# METR4810_Schematic.net
KiCad netlist of a schematic drawn in Altium Designer
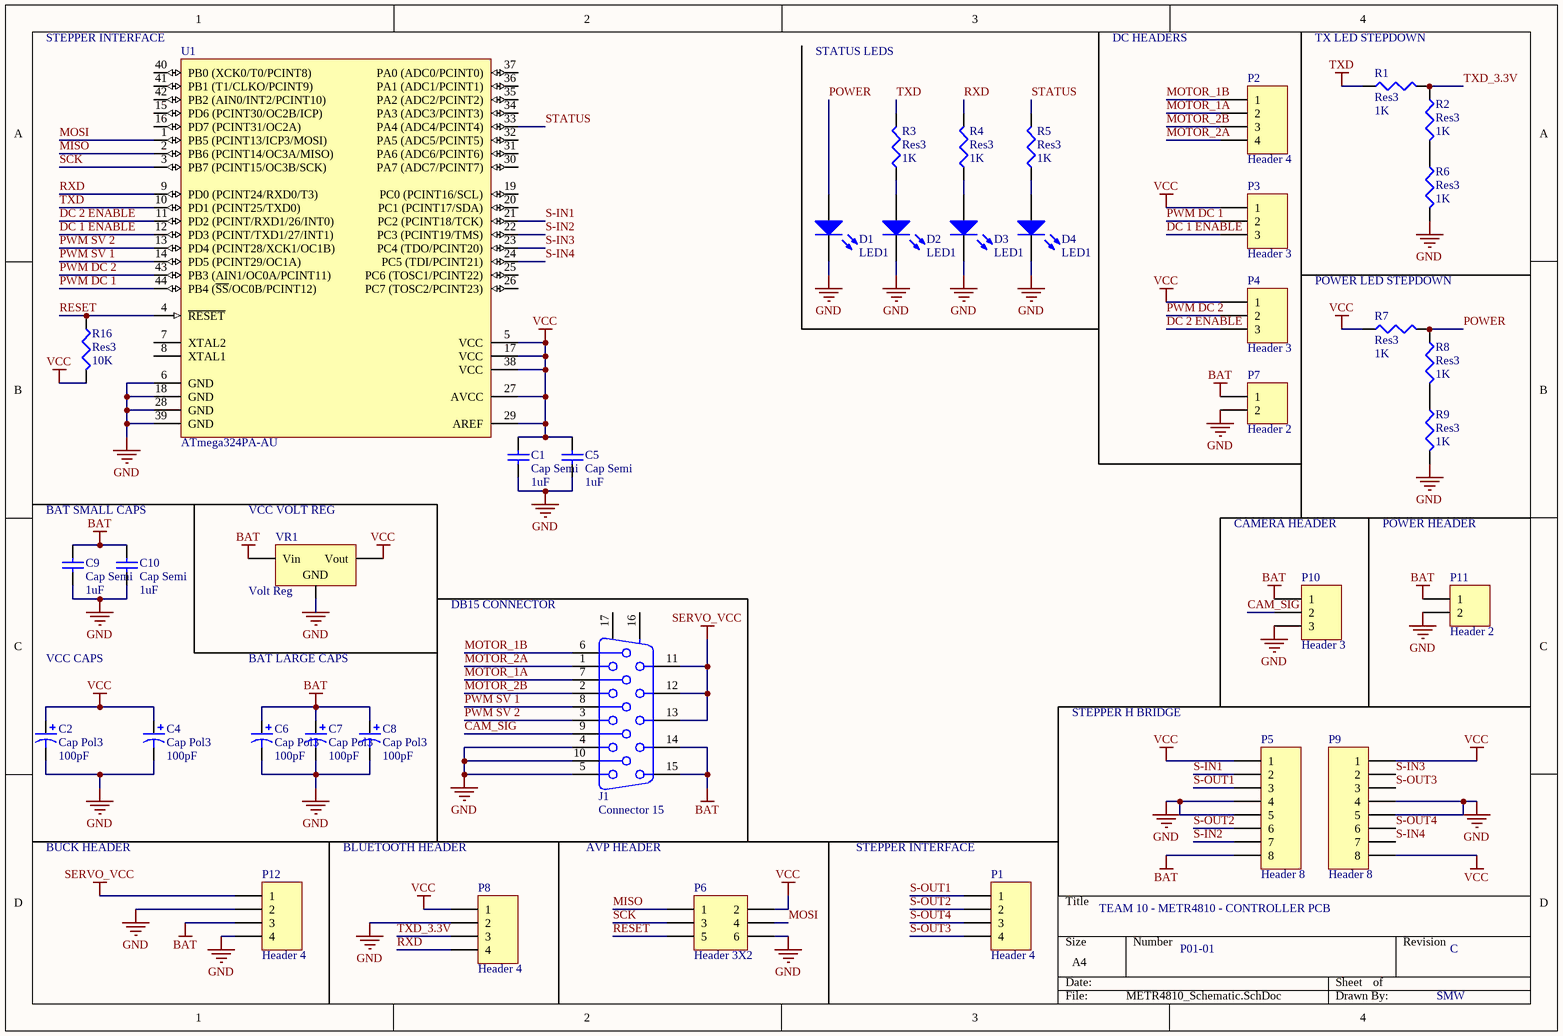
[diagram p0: METR4810_Schematic.SchDoc]

(export (version "E")
  (design (tool "Eeschema 10.0.6"))
  (components
    (comp (ref "C1")
      (value "Cap Semi")
      (footprint "C1206")
      (description "Capacitor (Semiconductor SIM Model)")
      (fields (field (name "ALTIUM_VALUE") "1uF") (field (name "PUBLISHER") "Altium Limited"))
      (libsource (lib "Miscellaneous Devices") (part "Cap Semi"))
    )
    (comp (ref "C2")
      (value "Cap Pol3")
      (footprint "C0805")
      (description "Polarized Capacitor (Surface Mount)")
      (fields (field (name "ALTIUM_VALUE") "100pF") (field (name "PUBLISHER") "Altium Limited"))
      (libsource (lib "Miscellaneous Devices") (part "Cap Pol3"))
    )
    (comp (ref "C4")
      (value "Cap Pol3")
      (footprint "C0805")
      (description "Polarized Capacitor (Surface Mount)")
      (fields (field (name "ALTIUM_VALUE") "100pF") (field (name "PUBLISHER") "Altium Limited"))
      (libsource (lib "Miscellaneous Devices") (part "Cap Pol3"))
    )
    (comp (ref "C5")
      (value "Cap Semi")
      (footprint "C1206")
      (description "Capacitor (Semiconductor SIM Model)")
      (fields (field (name "ALTIUM_VALUE") "1uF") (field (name "PUBLISHER") "Altium Limited"))
      (libsource (lib "Miscellaneous Devices") (part "Cap Semi"))
    )
    (comp (ref "C6")
      (value "Cap Pol3")
      (footprint "C0805")
      (description "Polarized Capacitor (Surface Mount)")
      (fields (field (name "ALTIUM_VALUE") "100pF") (field (name "PUBLISHER") "Altium Limited"))
      (libsource (lib "Miscellaneous Devices") (part "Cap Pol3"))
    )
    (comp (ref "C7")
      (value "Cap Pol3")
      (footprint "C0805")
      (description "Polarized Capacitor (Surface Mount)")
      (fields (field (name "ALTIUM_VALUE") "100pF") (field (name "PUBLISHER") "Altium Limited"))
      (libsource (lib "Miscellaneous Devices") (part "Cap Pol3"))
    )
    (comp (ref "C8")
      (value "Cap Pol3")
      (footprint "C0805")
      (description "Polarized Capacitor (Surface Mount)")
      (fields (field (name "ALTIUM_VALUE") "100pF") (field (name "PUBLISHER") "Altium Limited"))
      (libsource (lib "Miscellaneous Devices") (part "Cap Pol3"))
    )
    (comp (ref "C9")
      (value "Cap Semi")
      (footprint "C1206")
      (description "Capacitor (Semiconductor SIM Model)")
      (fields (field (name "ALTIUM_VALUE") "1uF") (field (name "PUBLISHER") "Altium Limited"))
      (libsource (lib "Miscellaneous Devices") (part "Cap Semi"))
    )
    (comp (ref "C10")
      (value "Cap Semi")
      (footprint "C1206")
      (description "Capacitor (Semiconductor SIM Model)")
      (fields (field (name "ALTIUM_VALUE") "1uF") (field (name "PUBLISHER") "Altium Limited"))
      (libsource (lib "Miscellaneous Devices") (part "Cap Semi"))
    )
    (comp (ref "D1")
      (value "LED1")
      (footprint "L0603")
      (description "Typical RED GaAs LED")
      (fields (field (name "PUBLISHER") "Altium Limited"))
      (libsource (lib "Miscellaneous Devices") (part "LED1"))
    )
    (comp (ref "D2")
      (value "LED1")
      (footprint "L0603")
      (description "Typical RED GaAs LED")
      (fields (field (name "PUBLISHER") "Altium Limited"))
      (libsource (lib "Miscellaneous Devices") (part "LED1"))
    )
    (comp (ref "D3")
      (value "LED1")
      (footprint "L0603")
      (description "Typical RED GaAs LED")
      (fields (field (name "PUBLISHER") "Altium Limited"))
      (libsource (lib "Miscellaneous Devices") (part "LED1"))
    )
    (comp (ref "D4")
      (value "LED1")
      (footprint "L0603")
      (description "Typical RED GaAs LED")
      (fields (field (name "PUBLISHER") "Altium Limited"))
      (libsource (lib "Miscellaneous Devices") (part "LED1"))
    )
    (comp (ref "J1")
      (value "Connector 15")
      (footprint "VGA_F:PCBComponent_1")
      (description "Receptacle Assembly, 15-Pin, Sim Line Connector")
      (fields (field (name "PUBLISHER") "Altium Limited"))
      (libsource (lib "Miscellaneous Connectors") (part "Connector 15"))
    )
    (comp (ref "P1")
      (value "Header 4")
      (footprint "HDR1X4")
      (description "Header, 4-Pin")
      (fields (field (name "PUBLISHER") "Altium Limited"))
      (libsource (lib "Miscellaneous Connectors") (part "Header 4"))
    )
    (comp (ref "P2")
      (value "Header 4")
      (footprint "HDR1X4")
      (description "Header, 4-Pin")
      (fields (field (name "PUBLISHER") "Altium Limited"))
      (libsource (lib "Miscellaneous Connectors") (part "Header 4"))
    )
    (comp (ref "P3")
      (value "Header 3")
      (footprint "HDR1X3")
      (description "Header, 3-Pin")
      (fields (field (name "PUBLISHER") "Altium Limited"))
      (libsource (lib "Miscellaneous Connectors") (part "Header 3"))
    )
    (comp (ref "P4")
      (value "Header 3")
      (footprint "HDR1X3")
      (description "Header, 3-Pin")
      (fields (field (name "PUBLISHER") "Altium Limited"))
      (libsource (lib "Miscellaneous Connectors") (part "Header 3"))
    )
    (comp (ref "P5")
      (value "Header 8")
      (footprint "HDR1X8")
      (description "Header, 8-Pin")
      (fields (field (name "PUBLISHER") "Altium Limited"))
      (libsource (lib "") (part "Header 8_1"))
    )
    (comp (ref "P6")
      (value "Header 3X2")
      (footprint "HDR2X3")
      (description "Header, 3-Pin, Dual row")
      (fields (field (name "PUBLISHER") "Altium Limited"))
      (libsource (lib "Miscellaneous Connectors") (part "Header 3X2"))
    )
    (comp (ref "P7")
      (value "Header 2")
      (footprint "HDR1X2")
      (description "Header, 2-Pin")
      (fields (field (name "PUBLISHER") "Altium Limited"))
      (libsource (lib "Miscellaneous Connectors") (part "Header 2"))
    )
    (comp (ref "P8")
      (value "Header 4")
      (footprint "HDR1X4")
      (description "Header, 4-Pin")
      (fields (field (name "PUBLISHER") "Altium Limited"))
      (libsource (lib "Miscellaneous Connectors") (part "Header 4"))
    )
    (comp (ref "P9")
      (value "Header 8")
      (footprint "HDR1X8")
      (description "Header, 8-Pin")
      (fields (field (name "PUBLISHER") "Altium Limited"))
      (libsource (lib "Miscellaneous Connectors") (part "Header 8"))
    )
    (comp (ref "P10")
      (value "Header 3")
      (footprint "HDR1X3")
      (description "Header, 3-Pin")
      (fields (field (name "PUBLISHER") "Altium Limited"))
      (libsource (lib "Miscellaneous Connectors") (part "Header 3"))
    )
    (comp (ref "P11")
      (value "Header 2")
      (footprint "HDR1X2")
      (description "Header, 2-Pin")
      (fields (field (name "PUBLISHER") "Altium Limited"))
      (libsource (lib "Miscellaneous Connectors") (part "Header 2"))
    )
    (comp (ref "P12")
      (value "Header 4")
      (footprint "HDR1X4")
      (description "Header, 4-Pin")
      (fields (field (name "PUBLISHER") "Altium Limited"))
      (libsource (lib "Miscellaneous Connectors") (part "Header 4"))
    )
    (comp (ref "R1")
      (value "Res3")
      (footprint "J1-0603")
      (description "Resistor")
      (fields (field (name "ALTIUM_VALUE") "1K") (field (name "PUBLISHER") "Altium Limited"))
      (libsource (lib "Miscellaneous Devices") (part "Res3"))
    )
    (comp (ref "R2")
      (value "Res3")
      (footprint "J1-0603")
      (description "Resistor")
      (fields (field (name "ALTIUM_VALUE") "1K") (field (name "PUBLISHER") "Altium Limited"))
      (libsource (lib "Miscellaneous Devices") (part "Res3"))
    )
    (comp (ref "R3")
      (value "Res3")
      (footprint "J1-0603")
      (description "Resistor")
      (fields (field (name "ALTIUM_VALUE") "1K") (field (name "PUBLISHER") "Altium Limited"))
      (libsource (lib "Miscellaneous Devices") (part "Res3"))
    )
    (comp (ref "R4")
      (value "Res3")
      (footprint "J1-0603")
      (description "Resistor")
      (fields (field (name "ALTIUM_VALUE") "1K") (field (name "PUBLISHER") "Altium Limited"))
      (libsource (lib "Miscellaneous Devices") (part "Res3"))
    )
    (comp (ref "R5")
      (value "Res3")
      (footprint "J1-0603")
      (description "Resistor")
      (fields (field (name "ALTIUM_VALUE") "1K") (field (name "PUBLISHER") "Altium Limited"))
      (libsource (lib "Miscellaneous Devices") (part "Res3"))
    )
    (comp (ref "R6")
      (value "Res3")
      (footprint "J1-0603")
      (description "Resistor")
      (fields (field (name "ALTIUM_VALUE") "1K") (field (name "PUBLISHER") "Altium Limited"))
      (libsource (lib "Miscellaneous Devices") (part "Res3"))
    )
    (comp (ref "R7")
      (value "Res3")
      (footprint "J1-0603")
      (description "Resistor")
      (fields (field (name "ALTIUM_VALUE") "1K") (field (name "PUBLISHER") "Altium Limited"))
      (libsource (lib "Miscellaneous Devices") (part "Res3"))
    )
    (comp (ref "R8")
      (value "Res3")
      (footprint "J1-0603")
      (description "Resistor")
      (fields (field (name "ALTIUM_VALUE") "1K") (field (name "PUBLISHER") "Altium Limited"))
      (libsource (lib "Miscellaneous Devices") (part "Res3"))
    )
    (comp (ref "R9")
      (value "Res3")
      (footprint "J1-0603")
      (description "Resistor")
      (fields (field (name "ALTIUM_VALUE") "1K") (field (name "PUBLISHER") "Altium Limited"))
      (libsource (lib "Miscellaneous Devices") (part "Res3"))
    )
    (comp (ref "R16")
      (value "Res3")
      (footprint "J1-0603")
      (description "Resistor")
      (fields (field (name "ALTIUM_VALUE") "10K") (field (name "PUBLISHER") "Altium Limited"))
      (libsource (lib "Miscellaneous Devices") (part "Res3"))
    )
    (comp (ref "U1")
      (value "ATmega324PA-AU")
      (footprint "44A_N")
      (libsource (lib "Atmel Microcontroller megaAVR") (part "ATmega324PA-AU"))
    )
    (comp (ref "VR1")
      (value "Volt Reg")
      (footprint "D2PAK_N")
      (description "Voltage Regulator")
      (fields (field (name "PUBLISHER") "Altium Limited"))
      (libsource (lib "Miscellaneous Devices") (part "Volt Reg"))
    )
  )
  (nets
    (net (code "1") (name "/CAM_SIG") (class "Default")
      (node (ref "J1") (pin "9") (pinfunction "9_9") (pintype "passive"))
      (node (ref "P10") (pin "2") (pinfunction "2_2") (pintype "passive"))
    )
    (net (code "2") (name "/DC 1 ENABLE") (class "Default")
      (node (ref "P3") (pin "3") (pinfunction "3_3") (pintype "passive"))
      (node (ref "U1") (pin "12") (pinfunction "PD3_(PCINT/TXD1/27/INT1)_12") (pintype "bidirectional"))
    )
    (net (code "3") (name "/DC 2 ENABLE") (class "Default")
      (node (ref "P4") (pin "3") (pinfunction "3_3") (pintype "passive"))
      (node (ref "U1") (pin "11") (pinfunction "PD2_(PCINT/RXD1/26/INT0)_11") (pintype "bidirectional"))
    )
    (net (code "4") (name "/MISO") (class "Default")
      (node (ref "P6") (pin "1") (pinfunction "1_1") (pintype "passive"))
      (node (ref "U1") (pin "2") (pinfunction "PB6_(PCINT14/OC3A/MISO)_2") (pintype "bidirectional"))
    )
    (net (code "5") (name "/MOSI") (class "Default")
      (node (ref "P6") (pin "4") (pinfunction "4_4") (pintype "passive"))
      (node (ref "U1") (pin "1") (pinfunction "PB5_(PCINT13/ICP3/MOSI)_1") (pintype "bidirectional"))
    )
    (net (code "6") (name "/MOTOR_1A") (class "Default")
      (node (ref "J1") (pin "7") (pinfunction "7_7") (pintype "passive"))
      (node (ref "P2") (pin "2") (pinfunction "2_2") (pintype "passive"))
    )
    (net (code "7") (name "/MOTOR_1B") (class "Default")
      (node (ref "J1") (pin "6") (pinfunction "6_6") (pintype "passive"))
      (node (ref "P2") (pin "1") (pinfunction "1_1") (pintype "passive"))
    )
    (net (code "8") (name "/MOTOR_2A") (class "Default")
      (node (ref "J1") (pin "1") (pinfunction "1_1") (pintype "passive"))
      (node (ref "P2") (pin "4") (pinfunction "4_4") (pintype "passive"))
    )
    (net (code "9") (name "/MOTOR_2B") (class "Default")
      (node (ref "J1") (pin "2") (pinfunction "2_2") (pintype "passive"))
      (node (ref "P2") (pin "3") (pinfunction "3_3") (pintype "passive"))
    )
    (net (code "10") (name "/POWER") (class "Default")
      (node (ref "D1") (pin "1") (pinfunction "A_1") (pintype "passive"))
      (node (ref "R7") (pin "2") (pinfunction "2_2") (pintype "passive"))
      (node (ref "R8") (pin "1") (pinfunction "1_1") (pintype "passive"))
    )
    (net (code "11") (name "/PWM DC 1") (class "Default")
      (node (ref "P3") (pin "2") (pinfunction "2_2") (pintype "passive"))
      (node (ref "U1") (pin "44") (pinfunction "PB4_(~{SS}/OC0B/PCINT12)_44") (pintype "bidirectional"))
    )
    (net (code "12") (name "/PWM DC 2") (class "Default")
      (node (ref "P4") (pin "2") (pinfunction "2_2") (pintype "passive"))
      (node (ref "U1") (pin "43") (pinfunction "PB3_(AIN1/OC0A/PCINT11)_43") (pintype "bidirectional"))
    )
    (net (code "13") (name "/PWM SV 1") (class "Default")
      (node (ref "J1") (pin "8") (pinfunction "8_8") (pintype "passive"))
      (node (ref "U1") (pin "14") (pinfunction "PD5_(PCINT29/OC1A)_14") (pintype "bidirectional"))
    )
    (net (code "14") (name "/PWM SV 2") (class "Default")
      (node (ref "J1") (pin "3") (pinfunction "3_3") (pintype "passive"))
      (node (ref "U1") (pin "13") (pinfunction "PD4_(PCINT28/XCK1/OC1B)_13") (pintype "bidirectional"))
    )
    (net (code "15") (name "/RESET") (class "Default")
      (node (ref "P6") (pin "5") (pinfunction "5_5") (pintype "passive"))
      (node (ref "R16") (pin "1") (pinfunction "1_1") (pintype "passive"))
      (node (ref "U1") (pin "4") (pinfunction "~{RESET}_4") (pintype "input"))
    )
    (net (code "16") (name "/RXD") (class "Default")
      (node (ref "P8") (pin "4") (pinfunction "4_4") (pintype "passive"))
      (node (ref "R4") (pin "2") (pinfunction "2_2") (pintype "passive"))
      (node (ref "U1") (pin "9") (pinfunction "PD0_(PCINT24/RXD0/T3)_9") (pintype "bidirectional"))
    )
    (net (code "17") (name "/S-IN1") (class "Default")
      (node (ref "P5") (pin "2") (pinfunction "2_2") (pintype "passive"))
      (node (ref "U1") (pin "21") (pinfunction "PC2_(PCINT18/TCK)_21") (pintype "bidirectional"))
    )
    (net (code "18") (name "/S-IN2") (class "Default")
      (node (ref "P5") (pin "7") (pinfunction "7_7") (pintype "passive"))
      (node (ref "U1") (pin "22") (pinfunction "PC3_(PCINT19/TMS)_22") (pintype "bidirectional"))
    )
    (net (code "19") (name "/S-IN3") (class "Default")
      (node (ref "P9") (pin "2") (pinfunction "2_2") (pintype "passive"))
      (node (ref "U1") (pin "23") (pinfunction "PC4_(TDO/PCINT20)_23") (pintype "bidirectional"))
    )
    (net (code "20") (name "/S-IN4") (class "Default")
      (node (ref "P9") (pin "7") (pinfunction "7_7") (pintype "passive"))
      (node (ref "U1") (pin "24") (pinfunction "PC5_(TDI/PCINT21)_24") (pintype "bidirectional"))
    )
    (net (code "21") (name "/S-OUT1") (class "Default")
      (node (ref "P1") (pin "1") (pinfunction "1_1") (pintype "passive"))
      (node (ref "P5") (pin "3") (pinfunction "3_3") (pintype "passive"))
    )
    (net (code "22") (name "/S-OUT2") (class "Default")
      (node (ref "P1") (pin "2") (pinfunction "2_2") (pintype "passive"))
      (node (ref "P5") (pin "6") (pinfunction "6_6") (pintype "passive"))
    )
    (net (code "23") (name "/S-OUT3") (class "Default")
      (node (ref "P1") (pin "4") (pinfunction "4_4") (pintype "passive"))
      (node (ref "P9") (pin "3") (pinfunction "3_3") (pintype "passive"))
    )
    (net (code "24") (name "/S-OUT4") (class "Default")
      (node (ref "P1") (pin "3") (pinfunction "3_3") (pintype "passive"))
      (node (ref "P9") (pin "6") (pinfunction "6_6") (pintype "passive"))
    )
    (net (code "25") (name "/SCK") (class "Default")
      (node (ref "P6") (pin "3") (pinfunction "3_3") (pintype "passive"))
      (node (ref "U1") (pin "3") (pinfunction "PB7_(PCINT15/OC3B/SCK)_3") (pintype "bidirectional"))
    )
    (net (code "26") (name "/STATUS") (class "Default")
      (node (ref "R5") (pin "2") (pinfunction "2_2") (pintype "passive"))
      (node (ref "U1") (pin "33") (pinfunction "PA4_(ADC4/PCINT4)_33") (pintype "bidirectional"))
    )
    (net (code "27") (name "/TXD_3.3V") (class "Default")
      (node (ref "P8") (pin "3") (pinfunction "3_3") (pintype "passive"))
      (node (ref "R1") (pin "2") (pinfunction "2_2") (pintype "passive"))
      (node (ref "R2") (pin "1") (pinfunction "1_1") (pintype "passive"))
    )
    (net (code "28") (name "BAT") (class "Default")
      (node (ref "C10") (pin "2") (pinfunction "2_2") (pintype "passive"))
      (node (ref "C6") (pin "1") (pinfunction "1_1") (pintype "passive"))
      (node (ref "C7") (pin "1") (pinfunction "1_1") (pintype "passive"))
      (node (ref "C8") (pin "1") (pinfunction "1_1") (pintype "passive"))
      (node (ref "C9") (pin "2") (pinfunction "2_2") (pintype "passive"))
      (node (ref "J1") (pin "14") (pinfunction "14_14") (pintype "passive"))
      (node (ref "J1") (pin "15") (pinfunction "15_15") (pintype "passive"))
      (node (ref "P10") (pin "1") (pinfunction "1_1") (pintype "passive"))
      (node (ref "P11") (pin "1") (pinfunction "1_1") (pintype "passive"))
      (node (ref "P12") (pin "3") (pinfunction "3_3") (pintype "passive"))
      (node (ref "P5") (pin "8") (pinfunction "8_8") (pintype "passive"))
      (node (ref "P7") (pin "1") (pinfunction "1_1") (pintype "passive"))
      (node (ref "VR1") (pin "1") (pinfunction "Vin_1") (pintype "passive"))
    )
    (net (code "29") (name "GND") (class "Default")
      (node (ref "C1") (pin "1") (pinfunction "1_1") (pintype "passive"))
      (node (ref "C10") (pin "1") (pinfunction "1_1") (pintype "passive"))
      (node (ref "C2") (pin "2") (pinfunction "2_2") (pintype "passive"))
      (node (ref "C4") (pin "2") (pinfunction "2_2") (pintype "passive"))
      (node (ref "C5") (pin "1") (pinfunction "1_1") (pintype "passive"))
      (node (ref "C6") (pin "2") (pinfunction "2_2") (pintype "passive"))
      (node (ref "C7") (pin "2") (pinfunction "2_2") (pintype "passive"))
      (node (ref "C8") (pin "2") (pinfunction "2_2") (pintype "passive"))
      (node (ref "C9") (pin "1") (pinfunction "1_1") (pintype "passive"))
      (node (ref "D1") (pin "2") (pinfunction "K_2") (pintype "passive"))
      (node (ref "D2") (pin "2") (pinfunction "K_2") (pintype "passive"))
      (node (ref "D3") (pin "2") (pinfunction "K_2") (pintype "passive"))
      (node (ref "D4") (pin "2") (pinfunction "K_2") (pintype "passive"))
      (node (ref "J1") (pin "10") (pinfunction "10_10") (pintype "passive"))
      (node (ref "J1") (pin "4") (pinfunction "4_4") (pintype "passive"))
      (node (ref "J1") (pin "5") (pinfunction "5_5") (pintype "passive"))
      (node (ref "P10") (pin "3") (pinfunction "3_3") (pintype "passive"))
      (node (ref "P11") (pin "2") (pinfunction "2_2") (pintype "passive"))
      (node (ref "P12") (pin "2") (pinfunction "2_2") (pintype "passive"))
      (node (ref "P12") (pin "4") (pinfunction "4_4") (pintype "passive"))
      (node (ref "P5") (pin "4") (pinfunction "4_4") (pintype "passive"))
      (node (ref "P5") (pin "5") (pinfunction "5_5") (pintype "passive"))
      (node (ref "P6") (pin "6") (pinfunction "6_6") (pintype "passive"))
      (node (ref "P7") (pin "2") (pinfunction "2_2") (pintype "passive"))
      (node (ref "P8") (pin "2") (pinfunction "2_2") (pintype "passive"))
      (node (ref "P9") (pin "4") (pinfunction "4_4") (pintype "passive"))
      (node (ref "P9") (pin "5") (pinfunction "5_5") (pintype "passive"))
      (node (ref "R6") (pin "2") (pinfunction "2_2") (pintype "passive"))
      (node (ref "R9") (pin "2") (pinfunction "2_2") (pintype "passive"))
      (node (ref "U1") (pin "18") (pinfunction "GND_18") (pintype "power_in"))
      (node (ref "U1") (pin "28") (pinfunction "GND_28") (pintype "power_in"))
      (node (ref "U1") (pin "39") (pinfunction "GND_39") (pintype "power_in"))
      (node (ref "U1") (pin "6") (pinfunction "GND_6") (pintype "power_in"))
      (node (ref "VR1") (pin "2") (pinfunction "GND_2") (pintype "passive"))
    )
    (net (code "30") (name "Net-(D2-A)") (class "Default")
      (node (ref "D2") (pin "1") (pinfunction "A_1") (pintype "passive"))
      (node (ref "R3") (pin "1") (pinfunction "1_1") (pintype "passive"))
    )
    (net (code "31") (name "Net-(D3-A)") (class "Default")
      (node (ref "D3") (pin "1") (pinfunction "A_1") (pintype "passive"))
      (node (ref "R4") (pin "1") (pinfunction "1_1") (pintype "passive"))
    )
    (net (code "32") (name "Net-(D4-A)") (class "Default")
      (node (ref "D4") (pin "1") (pinfunction "A_1") (pintype "passive"))
      (node (ref "R5") (pin "1") (pinfunction "1_1") (pintype "passive"))
    )
    (net (code "33") (name "Net-(R2-Pad2)") (class "Default")
      (node (ref "R2") (pin "2") (pinfunction "2_2") (pintype "passive"))
      (node (ref "R6") (pin "1") (pinfunction "1_1") (pintype "passive"))
    )
    (net (code "34") (name "Net-(R8-Pad2)") (class "Default")
      (node (ref "R8") (pin "2") (pinfunction "2_2") (pintype "passive"))
      (node (ref "R9") (pin "1") (pinfunction "1_1") (pintype "passive"))
    )
    (net (code "35") (name "SERVO_VCC") (class "Default")
      (node (ref "J1") (pin "11") (pinfunction "11_11") (pintype "passive"))
      (node (ref "J1") (pin "12") (pinfunction "12_12") (pintype "passive"))
      (node (ref "J1") (pin "13") (pinfunction "13_13") (pintype "passive"))
      (node (ref "P12") (pin "1") (pinfunction "1_1") (pintype "passive"))
    )
    (net (code "36") (name "TXD") (class "Default")
      (node (ref "R1") (pin "1") (pinfunction "1_1") (pintype "passive"))
      (node (ref "R3") (pin "2") (pinfunction "2_2") (pintype "passive"))
      (node (ref "U1") (pin "10") (pinfunction "PD1_(PCINT25/TXD0)_10") (pintype "bidirectional"))
    )
    (net (code "37") (name "VCC") (class "Default")
      (node (ref "C1") (pin "2") (pinfunction "2_2") (pintype "passive"))
      (node (ref "C2") (pin "1") (pinfunction "1_1") (pintype "passive"))
      (node (ref "C4") (pin "1") (pinfunction "1_1") (pintype "passive"))
      (node (ref "C5") (pin "2") (pinfunction "2_2") (pintype "passive"))
      (node (ref "P3") (pin "1") (pinfunction "1_1") (pintype "passive"))
      (node (ref "P4") (pin "1") (pinfunction "1_1") (pintype "passive"))
      (node (ref "P5") (pin "1") (pinfunction "1_1") (pintype "passive"))
      (node (ref "P6") (pin "2") (pinfunction "2_2") (pintype "passive"))
      (node (ref "P8") (pin "1") (pinfunction "1_1") (pintype "passive"))
      (node (ref "P9") (pin "1") (pinfunction "1_1") (pintype "passive"))
      (node (ref "P9") (pin "8") (pinfunction "8_8") (pintype "passive"))
      (node (ref "R16") (pin "2") (pinfunction "2_2") (pintype "passive"))
      (node (ref "R7") (pin "1") (pinfunction "1_1") (pintype "passive"))
      (node (ref "U1") (pin "17") (pinfunction "VCC_17") (pintype "power_in"))
      (node (ref "U1") (pin "27") (pinfunction "AVCC_27") (pintype "power_in"))
      (node (ref "U1") (pin "29") (pinfunction "AREF_29") (pintype "power_in"))
      (node (ref "U1") (pin "38") (pinfunction "VCC_38") (pintype "power_in"))
      (node (ref "U1") (pin "5") (pinfunction "VCC_5") (pintype "power_in"))
      (node (ref "VR1") (pin "3") (pinfunction "Vout_3") (pintype "passive"))
    )
    (net (code "38") (name "unconnected-(J1-MH1-Pad16)") (class "Default")
      (node (ref "J1") (pin "16") (pinfunction "MH1_16") (pintype "passive"))
    )
    (net (code "39") (name "unconnected-(J1-MH2-Pad17)") (class "Default")
      (node (ref "J1") (pin "17") (pinfunction "MH2_17") (pintype "passive"))
    )
    (net (code "40") (name "unconnected-(U1-PA0_(ADC0{slash}PCINT0)-Pad37)") (class "Default")
      (node (ref "U1") (pin "37") (pinfunction "PA0_(ADC0/PCINT0)_37") (pintype "bidirectional"))
    )
    (net (code "41") (name "unconnected-(U1-PA1_(ADC1{slash}PCINT1)-Pad36)") (class "Default")
      (node (ref "U1") (pin "36") (pinfunction "PA1_(ADC1/PCINT1)_36") (pintype "bidirectional"))
    )
    (net (code "42") (name "unconnected-(U1-PA2_(ADC2{slash}PCINT2)-Pad35)") (class "Default")
      (node (ref "U1") (pin "35") (pinfunction "PA2_(ADC2/PCINT2)_35") (pintype "bidirectional"))
    )
    (net (code "43") (name "unconnected-(U1-PA3_(ADC3{slash}PCINT3)-Pad34)") (class "Default")
      (node (ref "U1") (pin "34") (pinfunction "PA3_(ADC3/PCINT3)_34") (pintype "bidirectional"))
    )
    (net (code "44") (name "unconnected-(U1-PA5_(ADC5{slash}PCINT5)-Pad32)") (class "Default")
      (node (ref "U1") (pin "32") (pinfunction "PA5_(ADC5/PCINT5)_32") (pintype "bidirectional"))
    )
    (net (code "45") (name "unconnected-(U1-PA6_(ADC6{slash}PCINT6)-Pad31)") (class "Default")
      (node (ref "U1") (pin "31") (pinfunction "PA6_(ADC6/PCINT6)_31") (pintype "bidirectional"))
    )
    (net (code "46") (name "unconnected-(U1-PA7_(ADC7{slash}PCINT7)-Pad30)") (class "Default")
      (node (ref "U1") (pin "30") (pinfunction "PA7_(ADC7/PCINT7)_30") (pintype "bidirectional"))
    )
    (net (code "47") (name "unconnected-(U1-PB0_(XCK0{slash}T0{slash}PCINT8)-Pad40)") (class "Default")
      (node (ref "U1") (pin "40") (pinfunction "PB0_(XCK0/T0/PCINT8)_40") (pintype "bidirectional"))
    )
    (net (code "48") (name "unconnected-(U1-PB1_(T1{slash}CLKO{slash}PCINT9)-Pad41)") (class "Default")
      (node (ref "U1") (pin "41") (pinfunction "PB1_(T1/CLKO/PCINT9)_41") (pintype "bidirectional"))
    )
    (net (code "49") (name "unconnected-(U1-PB2_(AIN0{slash}INT2{slash}PCINT10)-Pad42)") (class "Default")
      (node (ref "U1") (pin "42") (pinfunction "PB2_(AIN0/INT2/PCINT10)_42") (pintype "bidirectional"))
    )
    (net (code "50") (name "unconnected-(U1-PC0_(PCINT16{slash}SCL)-Pad19)") (class "Default")
      (node (ref "U1") (pin "19") (pinfunction "PC0_(PCINT16/SCL)_19") (pintype "bidirectional"))
    )
    (net (code "51") (name "unconnected-(U1-PC1_(PCINT17{slash}SDA)-Pad20)") (class "Default")
      (node (ref "U1") (pin "20") (pinfunction "PC1_(PCINT17/SDA)_20") (pintype "bidirectional"))
    )
    (net (code "52") (name "unconnected-(U1-PC6_(TOSC1{slash}PCINT22)-Pad25)") (class "Default")
      (node (ref "U1") (pin "25") (pinfunction "PC6_(TOSC1/PCINT22)_25") (pintype "bidirectional"))
    )
    (net (code "53") (name "unconnected-(U1-PC7_(TOSC2{slash}PCINT23)-Pad26)") (class "Default")
      (node (ref "U1") (pin "26") (pinfunction "PC7_(TOSC2/PCINT23)_26") (pintype "bidirectional"))
    )
    (net (code "54") (name "unconnected-(U1-PD6_(PCINT30{slash}OC2B{slash}ICP)-Pad15)") (class "Default")
      (node (ref "U1") (pin "15") (pinfunction "PD6_(PCINT30/OC2B/ICP)_15") (pintype "bidirectional"))
    )
    (net (code "55") (name "unconnected-(U1-PD7_(PCINT31{slash}OC2A)-Pad16)") (class "Default")
      (node (ref "U1") (pin "16") (pinfunction "PD7_(PCINT31/OC2A)_16") (pintype "bidirectional"))
    )
    (net (code "56") (name "unconnected-(U1-XTAL1-Pad8)") (class "Default")
      (node (ref "U1") (pin "8") (pinfunction "XTAL1_8") (pintype "passive"))
    )
    (net (code "57") (name "unconnected-(U1-XTAL2-Pad7)") (class "Default")
      (node (ref "U1") (pin "7") (pinfunction "XTAL2_7") (pintype "passive"))
    )
  )
)
